# LED_strip_control.net
KiCad netlist of a schematic drawn in EAGLE
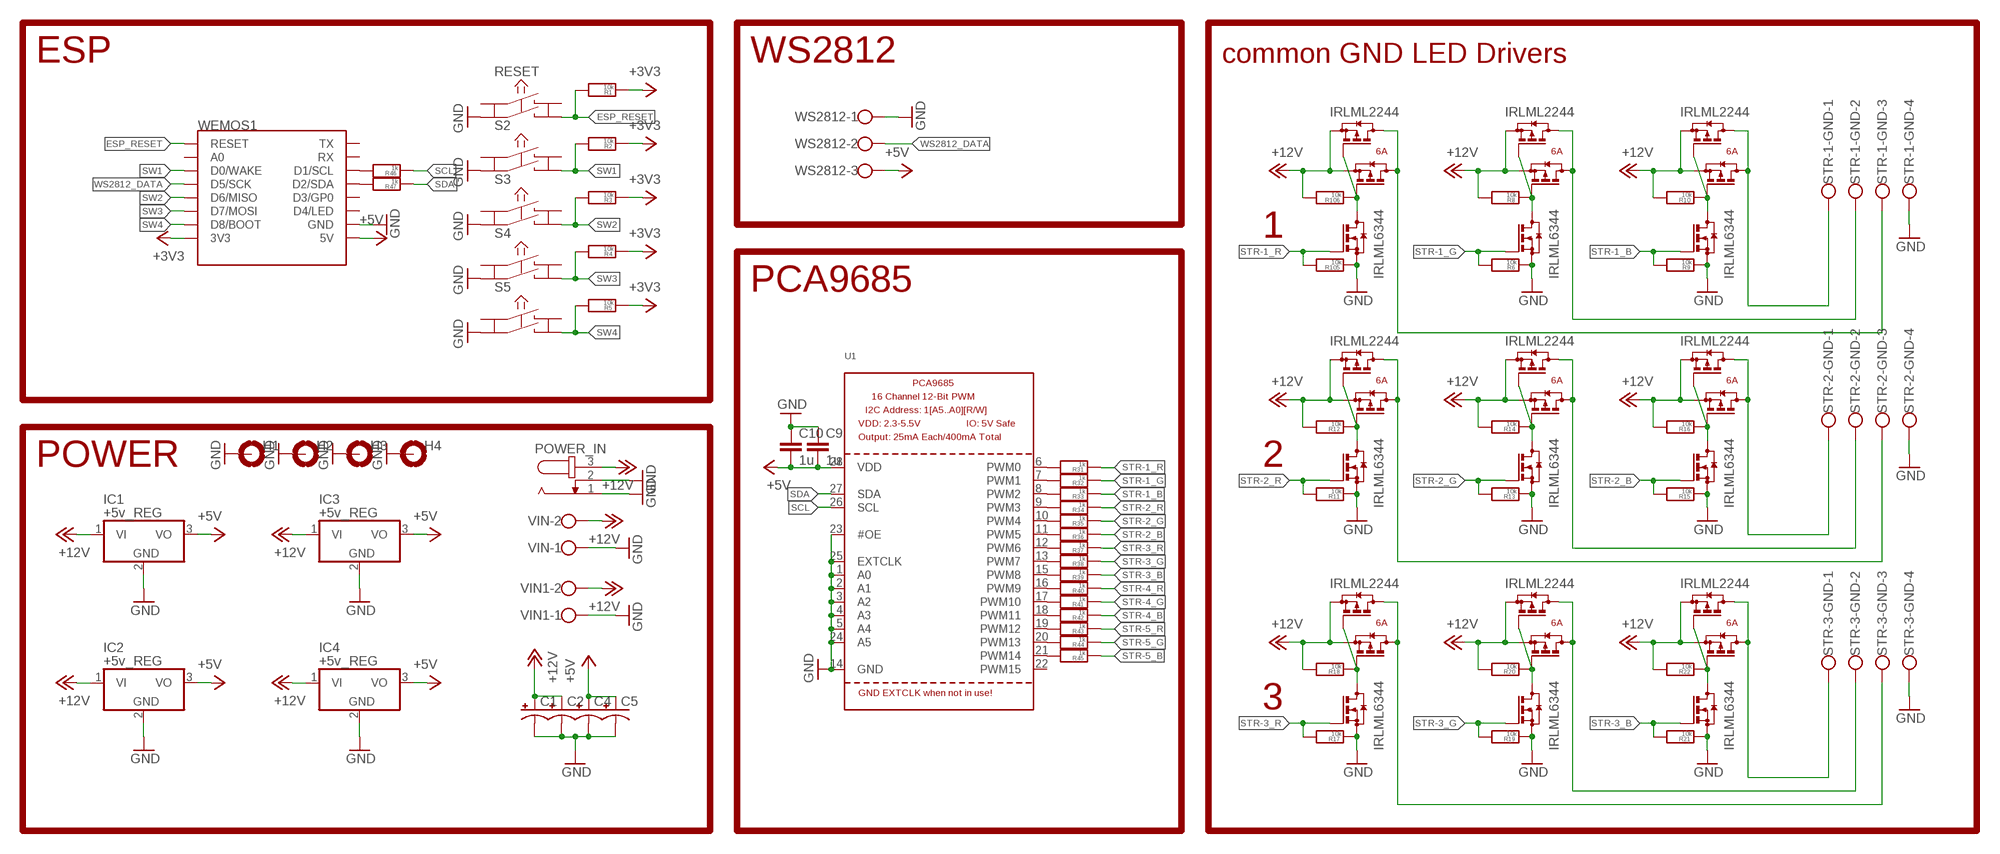
[diagram p0: schematic, sheet 1, part 1 of 2]
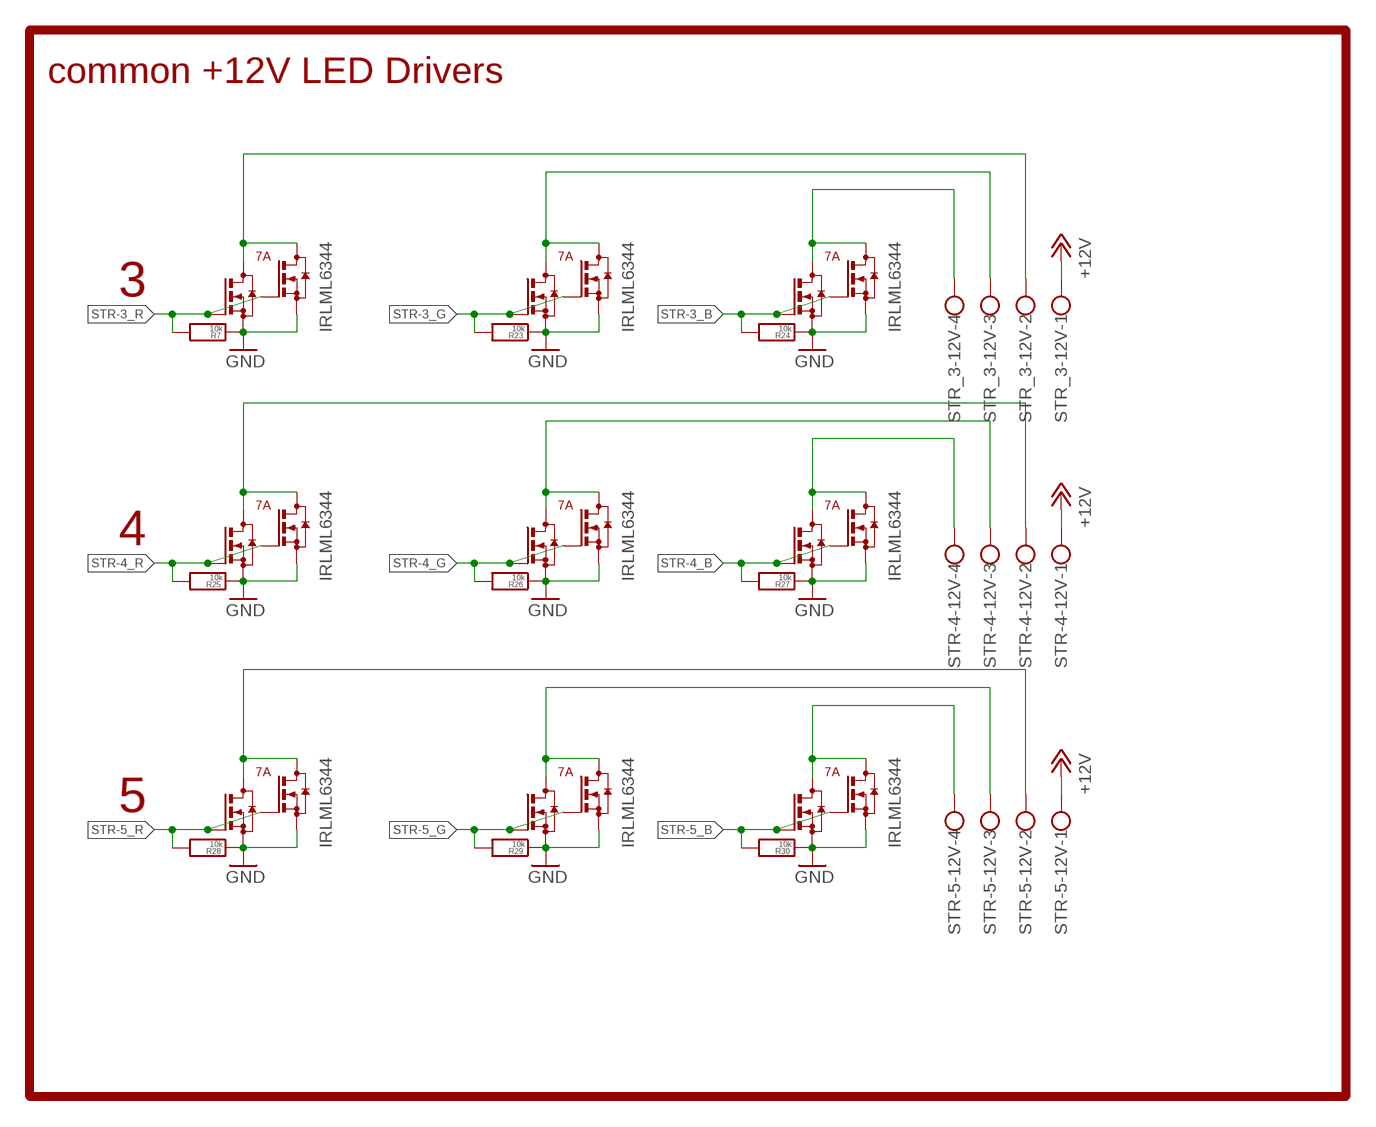
[diagram p1: schematic, sheet 1, part 2 of 2]

(export (version "E")
  (design (tool "Eeschema 10.0.6"))
  (components
    (comp (ref "C1")
      (value "CPOL-USE5-10.5")
      (footprint "eagle-import:E5-10,5@1")
      (libsource (lib "eagle-import") (part "CPOL-USE5-10.5"))
    )
    (comp (ref "C2")
      (value "CPOL-USE5-10.5")
      (footprint "eagle-import:E5-10,5@1")
      (libsource (lib "eagle-import") (part "CPOL-USE5-10.5"))
    )
    (comp (ref "C4")
      (value "CPOL-USE5-10.5")
      (footprint "eagle-import:E5-10,5@1")
      (libsource (lib "eagle-import") (part "CPOL-USE5-10.5"))
    )
    (comp (ref "C5")
      (value "CPOL-USE5-10.5")
      (footprint "eagle-import:E5-10,5@1")
      (libsource (lib "eagle-import") (part "CPOL-USE5-10.5"))
    )
    (comp (ref "C9")
      (value "1u")
      (footprint "eagle-import:C0805")
      (libsource (lib "eagle-import") (part "C-EUC0805"))
    )
    (comp (ref "C10")
      (value "1u")
      (footprint "eagle-import:C0805")
      (libsource (lib "eagle-import") (part "C-EUC0805"))
    )
    (comp (ref "H1")
      (value "MOUNT-PAD-ROUND3.2")
      (footprint "eagle-import:3,2-PAD")
      (libsource (lib "eagle-import") (part "MOUNT-PAD-ROUND3.2"))
    )
    (comp (ref "H2")
      (value "MOUNT-PAD-ROUND3.2")
      (footprint "eagle-import:3,2-PAD")
      (libsource (lib "eagle-import") (part "MOUNT-PAD-ROUND3.2"))
    )
    (comp (ref "H3")
      (value "MOUNT-PAD-ROUND3.2")
      (footprint "eagle-import:3,2-PAD")
      (libsource (lib "eagle-import") (part "MOUNT-PAD-ROUND3.2"))
    )
    (comp (ref "H4")
      (value "MOUNT-PAD-ROUND3.2")
      (footprint "eagle-import:3,2-PAD")
      (libsource (lib "eagle-import") (part "MOUNT-PAD-ROUND3.2"))
    )
    (comp (ref "IC1")
      (value "+5v_REG")
      (footprint "eagle-import:TO220V")
      (libsource (lib "eagle-import") (part "78TV6"))
    )
    (comp (ref "IC2")
      (value "+5v_REG")
      (footprint "eagle-import:TO220V")
      (libsource (lib "eagle-import") (part "78TV6"))
    )
    (comp (ref "IC3")
      (value "+5v_REG")
      (footprint "eagle-import:TO220V")
      (libsource (lib "eagle-import") (part "78TV6"))
    )
    (comp (ref "IC4")
      (value "+5v_REG")
      (footprint "eagle-import:TO220V")
      (libsource (lib "eagle-import") (part "78TV6"))
    )
    (comp (ref "POWER_IN")
      (value "RAPC7120")
      (footprint "eagle-import:RAPC712")
      (libsource (lib "eagle-import") (part "RAPC7120"))
    )
    (comp (ref "Q1")
      (value "IRLML2244")
      (footprint "eagle-import:SOT23")
      (libsource (lib "eagle-import") (part "BSS84"))
    )
    (comp (ref "Q2")
      (value "IRLML2244")
      (footprint "eagle-import:SOT23")
      (libsource (lib "eagle-import") (part "BSS84"))
    )
    (comp (ref "Q3")
      (value "IRLML6344")
      (footprint "eagle-import:SOT23")
      (libsource (lib "eagle-import") (part "BSS123"))
    )
    (comp (ref "Q4")
      (value "IRLML6344")
      (footprint "eagle-import:SOT23")
      (libsource (lib "eagle-import") (part "BSS123"))
    )
    (comp (ref "Q5")
      (value "IRLML6344")
      (footprint "eagle-import:SOT23")
      (libsource (lib "eagle-import") (part "BSS123"))
    )
    (comp (ref "Q6")
      (value "IRLML6344")
      (footprint "eagle-import:SOT23")
      (libsource (lib "eagle-import") (part "BSS123"))
    )
    (comp (ref "Q7")
      (value "IRLML2244")
      (footprint "eagle-import:SOT23")
      (libsource (lib "eagle-import") (part "BSS84"))
    )
    (comp (ref "Q8")
      (value "IRLML2244")
      (footprint "eagle-import:SOT23")
      (libsource (lib "eagle-import") (part "BSS84"))
    )
    (comp (ref "Q9")
      (value "IRLML6344")
      (footprint "eagle-import:SOT23")
      (libsource (lib "eagle-import") (part "BSS123"))
    )
    (comp (ref "Q10")
      (value "IRLML2244")
      (footprint "eagle-import:SOT23")
      (libsource (lib "eagle-import") (part "BSS84"))
    )
    (comp (ref "Q11")
      (value "IRLML2244")
      (footprint "eagle-import:SOT23")
      (libsource (lib "eagle-import") (part "BSS84"))
    )
    (comp (ref "Q12")
      (value "IRLML6344")
      (footprint "eagle-import:SOT23")
      (libsource (lib "eagle-import") (part "BSS123"))
    )
    (comp (ref "Q13")
      (value "IRLML2244")
      (footprint "eagle-import:SOT23")
      (libsource (lib "eagle-import") (part "BSS84"))
    )
    (comp (ref "Q14")
      (value "IRLML2244")
      (footprint "eagle-import:SOT23")
      (libsource (lib "eagle-import") (part "BSS84"))
    )
    (comp (ref "Q15")
      (value "IRLML6344")
      (footprint "eagle-import:SOT23")
      (libsource (lib "eagle-import") (part "BSS123"))
    )
    (comp (ref "Q16")
      (value "IRLML2244")
      (footprint "eagle-import:SOT23")
      (libsource (lib "eagle-import") (part "BSS84"))
    )
    (comp (ref "Q17")
      (value "IRLML2244")
      (footprint "eagle-import:SOT23")
      (libsource (lib "eagle-import") (part "BSS84"))
    )
    (comp (ref "Q18")
      (value "IRLML6344")
      (footprint "eagle-import:SOT23")
      (libsource (lib "eagle-import") (part "BSS123"))
    )
    (comp (ref "Q19")
      (value "IRLML2244")
      (footprint "eagle-import:SOT23")
      (libsource (lib "eagle-import") (part "BSS84"))
    )
    (comp (ref "Q20")
      (value "IRLML2244")
      (footprint "eagle-import:SOT23")
      (libsource (lib "eagle-import") (part "BSS84"))
    )
    (comp (ref "Q21")
      (value "IRLML6344")
      (footprint "eagle-import:SOT23")
      (libsource (lib "eagle-import") (part "BSS123"))
    )
    (comp (ref "Q22")
      (value "IRLML2244")
      (footprint "eagle-import:SOT23")
      (libsource (lib "eagle-import") (part "BSS84"))
    )
    (comp (ref "Q23")
      (value "IRLML2244")
      (footprint "eagle-import:SOT23")
      (libsource (lib "eagle-import") (part "BSS84"))
    )
    (comp (ref "Q24")
      (value "IRLML6344")
      (footprint "eagle-import:SOT23")
      (libsource (lib "eagle-import") (part "BSS123"))
    )
    (comp (ref "Q25")
      (value "IRLML2244")
      (footprint "eagle-import:SOT23")
      (libsource (lib "eagle-import") (part "BSS84"))
    )
    (comp (ref "Q26")
      (value "IRLML2244")
      (footprint "eagle-import:SOT23")
      (libsource (lib "eagle-import") (part "BSS84"))
    )
    (comp (ref "Q27")
      (value "IRLML6344")
      (footprint "eagle-import:SOT23")
      (libsource (lib "eagle-import") (part "BSS123"))
    )
    (comp (ref "Q28")
      (value "IRLML2244")
      (footprint "eagle-import:SOT23")
      (libsource (lib "eagle-import") (part "BSS84"))
    )
    (comp (ref "Q29")
      (value "IRLML2244")
      (footprint "eagle-import:SOT23")
      (libsource (lib "eagle-import") (part "BSS84"))
    )
    (comp (ref "Q30")
      (value "IRLML6344")
      (footprint "eagle-import:SOT23")
      (libsource (lib "eagle-import") (part "BSS123"))
    )
    (comp (ref "Q31")
      (value "IRLML6344")
      (footprint "eagle-import:SOT23")
      (libsource (lib "eagle-import") (part "BSS123"))
    )
    (comp (ref "Q32")
      (value "IRLML6344")
      (footprint "eagle-import:SOT23")
      (libsource (lib "eagle-import") (part "BSS123"))
    )
    (comp (ref "Q33")
      (value "IRLML6344")
      (footprint "eagle-import:SOT23")
      (libsource (lib "eagle-import") (part "BSS123"))
    )
    (comp (ref "Q34")
      (value "IRLML6344")
      (footprint "eagle-import:SOT23")
      (libsource (lib "eagle-import") (part "BSS123"))
    )
    (comp (ref "Q35")
      (value "IRLML6344")
      (footprint "eagle-import:SOT23")
      (libsource (lib "eagle-import") (part "BSS123"))
    )
    (comp (ref "Q36")
      (value "IRLML6344")
      (footprint "eagle-import:SOT23")
      (libsource (lib "eagle-import") (part "BSS123"))
    )
    (comp (ref "Q37")
      (value "IRLML6344")
      (footprint "eagle-import:SOT23")
      (libsource (lib "eagle-import") (part "BSS123"))
    )
    (comp (ref "Q38")
      (value "IRLML6344")
      (footprint "eagle-import:SOT23")
      (libsource (lib "eagle-import") (part "BSS123"))
    )
    (comp (ref "Q39")
      (value "IRLML6344")
      (footprint "eagle-import:SOT23")
      (libsource (lib "eagle-import") (part "BSS123"))
    )
    (comp (ref "Q40")
      (value "IRLML6344")
      (footprint "eagle-import:SOT23")
      (libsource (lib "eagle-import") (part "BSS123"))
    )
    (comp (ref "Q41")
      (value "IRLML6344")
      (footprint "eagle-import:SOT23")
      (libsource (lib "eagle-import") (part "BSS123"))
    )
    (comp (ref "Q42")
      (value "IRLML6344")
      (footprint "eagle-import:SOT23")
      (libsource (lib "eagle-import") (part "BSS123"))
    )
    (comp (ref "Q43")
      (value "IRLML6344")
      (footprint "eagle-import:SOT23")
      (libsource (lib "eagle-import") (part "BSS123"))
    )
    (comp (ref "Q44")
      (value "IRLML6344")
      (footprint "eagle-import:SOT23")
      (libsource (lib "eagle-import") (part "BSS123"))
    )
    (comp (ref "Q45")
      (value "IRLML6344")
      (footprint "eagle-import:SOT23")
      (libsource (lib "eagle-import") (part "BSS123"))
    )
    (comp (ref "R1")
      (value "10k")
      (footprint "eagle-import:R0805")
      (libsource (lib "eagle-import") (part "R-EU_R0805"))
    )
    (comp (ref "R2")
      (value "10k")
      (footprint "eagle-import:R0805")
      (libsource (lib "eagle-import") (part "R-EU_R0805"))
    )
    (comp (ref "R3")
      (value "10k")
      (footprint "eagle-import:R0805")
      (libsource (lib "eagle-import") (part "R-EU_R0805"))
    )
    (comp (ref "R4")
      (value "10k")
      (footprint "eagle-import:R0805")
      (libsource (lib "eagle-import") (part "R-EU_R0805"))
    )
    (comp (ref "R5")
      (value "10k")
      (footprint "eagle-import:R0805")
      (libsource (lib "eagle-import") (part "R-EU_R0805"))
    )
    (comp (ref "R6")
      (value "10k")
      (footprint "eagle-import:R0805")
      (libsource (lib "eagle-import") (part "R-EU_R0805"))
    )
    (comp (ref "R7")
      (value "10k")
      (footprint "eagle-import:R0805")
      (libsource (lib "eagle-import") (part "R-EU_R0805"))
    )
    (comp (ref "R8")
      (value "10k")
      (footprint "eagle-import:R0805")
      (libsource (lib "eagle-import") (part "R-EU_R0805"))
    )
    (comp (ref "R9")
      (value "10k")
      (footprint "eagle-import:R0805")
      (libsource (lib "eagle-import") (part "R-EU_R0805"))
    )
    (comp (ref "R10")
      (value "10k")
      (footprint "eagle-import:R0805")
      (libsource (lib "eagle-import") (part "R-EU_R0805"))
    )
    (comp (ref "R11")
      (value "10k")
      (footprint "eagle-import:R0805")
      (libsource (lib "eagle-import") (part "R-EU_R0805"))
    )
    (comp (ref "R12")
      (value "10k")
      (footprint "eagle-import:R0805")
      (libsource (lib "eagle-import") (part "R-EU_R0805"))
    )
    (comp (ref "R13")
      (value "10k")
      (footprint "eagle-import:R0805")
      (libsource (lib "eagle-import") (part "R-EU_R0805"))
    )
    (comp (ref "R14")
      (value "10k")
      (footprint "eagle-import:R0805")
      (libsource (lib "eagle-import") (part "R-EU_R0805"))
    )
    (comp (ref "R15")
      (value "10k")
      (footprint "eagle-import:R0805")
      (libsource (lib "eagle-import") (part "R-EU_R0805"))
    )
    (comp (ref "R16")
      (value "10k")
      (footprint "eagle-import:R0805")
      (libsource (lib "eagle-import") (part "R-EU_R0805"))
    )
    (comp (ref "R17")
      (value "10k")
      (footprint "eagle-import:R0805")
      (libsource (lib "eagle-import") (part "R-EU_R0805"))
    )
    (comp (ref "R18")
      (value "10k")
      (footprint "eagle-import:R0805")
      (libsource (lib "eagle-import") (part "R-EU_R0805"))
    )
    (comp (ref "R19")
      (value "10k")
      (footprint "eagle-import:R0805")
      (libsource (lib "eagle-import") (part "R-EU_R0805"))
    )
    (comp (ref "R20")
      (value "10k")
      (footprint "eagle-import:R0805")
      (libsource (lib "eagle-import") (part "R-EU_R0805"))
    )
    (comp (ref "R21")
      (value "10k")
      (footprint "eagle-import:R0805")
      (libsource (lib "eagle-import") (part "R-EU_R0805"))
    )
    (comp (ref "R22")
      (value "10k")
      (footprint "eagle-import:R0805")
      (libsource (lib "eagle-import") (part "R-EU_R0805"))
    )
    (comp (ref "R23")
      (value "10k")
      (footprint "eagle-import:R0805")
      (libsource (lib "eagle-import") (part "R-EU_R0805"))
    )
    (comp (ref "R24")
      (value "10k")
      (footprint "eagle-import:R0805")
      (libsource (lib "eagle-import") (part "R-EU_R0805"))
    )
    (comp (ref "R25")
      (value "10k")
      (footprint "eagle-import:R0805")
      (libsource (lib "eagle-import") (part "R-EU_R0805"))
    )
    (comp (ref "R26")
      (value "10k")
      (footprint "eagle-import:R0805")
      (libsource (lib "eagle-import") (part "R-EU_R0805"))
    )
    (comp (ref "R27")
      (value "10k")
      (footprint "eagle-import:R0805")
      (libsource (lib "eagle-import") (part "R-EU_R0805"))
    )
    (comp (ref "R28")
      (value "10k")
      (footprint "eagle-import:R0805")
      (libsource (lib "eagle-import") (part "R-EU_R0805"))
    )
    (comp (ref "R29")
      (value "10k")
      (footprint "eagle-import:R0805")
      (libsource (lib "eagle-import") (part "R-EU_R0805"))
    )
    (comp (ref "R30")
      (value "10k")
      (footprint "eagle-import:R0805")
      (libsource (lib "eagle-import") (part "R-EU_R0805"))
    )
    (comp (ref "R31")
      (value "1k")
      (footprint "eagle-import:R0805")
      (libsource (lib "eagle-import") (part "R-EU_R0805"))
    )
    (comp (ref "R32")
      (value "1k")
      (footprint "eagle-import:R0805")
      (libsource (lib "eagle-import") (part "R-EU_R0805"))
    )
    (comp (ref "R33")
      (value "1k")
      (footprint "eagle-import:R0805")
      (libsource (lib "eagle-import") (part "R-EU_R0805"))
    )
    (comp (ref "R34")
      (value "1k")
      (footprint "eagle-import:R0805")
      (libsource (lib "eagle-import") (part "R-EU_R0805"))
    )
    (comp (ref "R35")
      (value "1k")
      (footprint "eagle-import:R0805")
      (libsource (lib "eagle-import") (part "R-EU_R0805"))
    )
    (comp (ref "R36")
      (value "1k")
      (footprint "eagle-import:R0805")
      (libsource (lib "eagle-import") (part "R-EU_R0805"))
    )
    (comp (ref "R37")
      (value "1k")
      (footprint "eagle-import:R0805")
      (libsource (lib "eagle-import") (part "R-EU_R0805"))
    )
    (comp (ref "R38")
      (value "1k")
      (footprint "eagle-import:R0805")
      (libsource (lib "eagle-import") (part "R-EU_R0805"))
    )
    (comp (ref "R39")
      (value "1k")
      (footprint "eagle-import:R0805")
      (libsource (lib "eagle-import") (part "R-EU_R0805"))
    )
    (comp (ref "R40")
      (value "1k")
      (footprint "eagle-import:R0805")
      (libsource (lib "eagle-import") (part "R-EU_R0805"))
    )
    (comp (ref "R41")
      (value "1k")
      (footprint "eagle-import:R0805")
      (libsource (lib "eagle-import") (part "R-EU_R0805"))
    )
    (comp (ref "R42")
      (value "1k")
      (footprint "eagle-import:R0805")
      (libsource (lib "eagle-import") (part "R-EU_R0805"))
    )
    (comp (ref "R43")
      (value "1k")
      (footprint "eagle-import:R0805")
      (libsource (lib "eagle-import") (part "R-EU_R0805"))
    )
    (comp (ref "R44")
      (value "1k")
      (footprint "eagle-import:R0805")
      (libsource (lib "eagle-import") (part "R-EU_R0805"))
    )
    (comp (ref "R45")
      (value "1k")
      (footprint "eagle-import:R0805")
      (libsource (lib "eagle-import") (part "R-EU_R0805"))
    )
    (comp (ref "R46")
      (value "1k")
      (footprint "eagle-import:R0805")
      (libsource (lib "eagle-import") (part "R-EU_R0805"))
    )
    (comp (ref "R47")
      (value "1k")
      (footprint "eagle-import:R0805")
      (libsource (lib "eagle-import") (part "R-EU_R0805"))
    )
    (comp (ref "R105")
      (value "10k")
      (footprint "eagle-import:R0805")
      (libsource (lib "eagle-import") (part "R-EU_R0805"))
    )
    (comp (ref "R106")
      (value "10k")
      (footprint "eagle-import:R0805")
      (libsource (lib "eagle-import") (part "R-EU_R0805"))
    )
    (comp (ref "RESET")
      (value "KSM611A")
      (footprint "eagle-import:KSM611A")
      (libsource (lib "eagle-import") (part "KSM611A"))
    )
    (comp (ref "S2")
      (value "KSM611A")
      (footprint "eagle-import:KSM611A")
      (libsource (lib "eagle-import") (part "KSM611A"))
    )
    (comp (ref "S3")
      (value "KSM611A")
      (footprint "eagle-import:KSM611A")
      (libsource (lib "eagle-import") (part "KSM611A"))
    )
    (comp (ref "S4")
      (value "KSM611A")
      (footprint "eagle-import:KSM611A")
      (libsource (lib "eagle-import") (part "KSM611A"))
    )
    (comp (ref "S5")
      (value "KSM611A")
      (footprint "eagle-import:KSM611A")
      (libsource (lib "eagle-import") (part "KSM611A"))
    )
    (comp (ref "STR-1-GND")
      (value "KLEMME_4-PIN")
      (footprint "eagle-import:KLEMME_4-PIN")
      (libsource (lib "eagle-import") (part "KLEMME_4-PIN"))
    )
    (comp (ref "STR-2-GND")
      (value "KLEMME_4-PIN")
      (footprint "eagle-import:KLEMME_4-PIN")
      (libsource (lib "eagle-import") (part "KLEMME_4-PIN"))
    )
    (comp (ref "STR-3-GND")
      (value "KLEMME_4-PIN")
      (footprint "eagle-import:KLEMME_4-PIN")
      (libsource (lib "eagle-import") (part "KLEMME_4-PIN"))
    )
    (comp (ref "STR-4-12V")
      (value "KLEMME_4-PIN")
      (footprint "eagle-import:KLEMME_4-PIN")
      (libsource (lib "eagle-import") (part "KLEMME_4-PIN"))
    )
    (comp (ref "STR-5-12V")
      (value "KLEMME_4-PIN")
      (footprint "eagle-import:KLEMME_4-PIN")
      (libsource (lib "eagle-import") (part "KLEMME_4-PIN"))
    )
    (comp (ref "STR_3-12V")
      (value "KLEMME_4-PIN")
      (footprint "eagle-import:KLEMME_4-PIN")
      (libsource (lib "eagle-import") (part "KLEMME_4-PIN"))
    )
    (comp (ref "U1")
      (value "PCA9685")
      (footprint "eagle-import:TSSOP28")
      (libsource (lib "eagle-import") (part "PCA9685"))
    )
    (comp (ref "VIN")
      (value "W237-102")
      (footprint "eagle-import:W237-102")
      (fields (field (name "MPN") "237-102"))
      (libsource (lib "eagle-import") (part "W237-102"))
    )
    (comp (ref "VIN1")
      (value "W237-102")
      (footprint "eagle-import:W237-102")
      (fields (field (name "MPN") "237-102"))
      (libsource (lib "eagle-import") (part "W237-102"))
    )
    (comp (ref "WEMOS1")
      (value "WEMOS-D1-MINI")
      (footprint "eagle-import:WEMOS-D1-MINI")
      (libsource (lib "eagle-import") (part "WEMOS-D1-MINI"))
    )
    (comp (ref "WS2812")
      (value "KLEMME_3-PIN")
      (footprint "eagle-import:KLEMME_3-PIN")
      (libsource (lib "eagle-import") (part "KLEMME_3-PIN"))
    )
  )
  (nets
    (net (code "1") (name "+3V3") (class "Default")
      (node (ref "R1") (pin "1") (pinfunction "1_1") (pintype "passive"))
      (node (ref "R2") (pin "1") (pinfunction "1_1") (pintype "passive"))
      (node (ref "R3") (pin "1") (pinfunction "1_1") (pintype "passive"))
      (node (ref "R4") (pin "1") (pinfunction "1_1") (pintype "passive"))
      (node (ref "R5") (pin "1") (pinfunction "1_1") (pintype "passive"))
      (node (ref "WEMOS1") (pin "3V3") (pinfunction "3V3_3V3") (pintype "bidirectional"))
    )
    (net (code "2") (name "+5V") (class "Default")
      (node (ref "C10") (pin "2") (pinfunction "2_2") (pintype "passive"))
      (node (ref "C4") (pin "+") (pinfunction "+_+") (pintype "passive"))
      (node (ref "C5") (pin "+") (pinfunction "+_+") (pintype "passive"))
      (node (ref "C9") (pin "2") (pinfunction "2_2") (pintype "passive"))
      (node (ref "IC1") (pin "3") (pinfunction "VO_3") (pintype "passive"))
      (node (ref "IC2") (pin "3") (pinfunction "VO_3") (pintype "passive"))
      (node (ref "IC3") (pin "3") (pinfunction "VO_3") (pintype "passive"))
      (node (ref "IC4") (pin "3") (pinfunction "VO_3") (pintype "passive"))
      (node (ref "U1") (pin "28") (pinfunction "VDD_28") (pintype "power_in"))
      (node (ref "WEMOS1") (pin "5V") (pinfunction "5V_5V") (pintype "bidirectional"))
      (node (ref "WS2812") (pin "3") (pinfunction "KL_3") (pintype "passive"))
    )
    (net (code "3") (name "+12V") (class "Default")
      (node (ref "C1") (pin "+") (pinfunction "+_+") (pintype "passive"))
      (node (ref "C2") (pin "+") (pinfunction "+_+") (pintype "passive"))
      (node (ref "IC1") (pin "1") (pinfunction "VI_1") (pintype "input"))
      (node (ref "IC2") (pin "1") (pinfunction "VI_1") (pintype "input"))
      (node (ref "IC3") (pin "1") (pinfunction "VI_1") (pintype "input"))
      (node (ref "IC4") (pin "1") (pinfunction "VI_1") (pintype "input"))
      (node (ref "POWER_IN") (pin "3") (pinfunction "3_3") (pintype "passive"))
      (node (ref "Q1") (pin "2") (pinfunction "S_2") (pintype "passive"))
      (node (ref "Q10") (pin "2") (pinfunction "S_2") (pintype "passive"))
      (node (ref "Q11") (pin "2") (pinfunction "S_2") (pintype "passive"))
      (node (ref "Q13") (pin "2") (pinfunction "S_2") (pintype "passive"))
      (node (ref "Q14") (pin "2") (pinfunction "S_2") (pintype "passive"))
      (node (ref "Q16") (pin "2") (pinfunction "S_2") (pintype "passive"))
      (node (ref "Q17") (pin "2") (pinfunction "S_2") (pintype "passive"))
      (node (ref "Q19") (pin "2") (pinfunction "S_2") (pintype "passive"))
      (node (ref "Q2") (pin "2") (pinfunction "S_2") (pintype "passive"))
      (node (ref "Q20") (pin "2") (pinfunction "S_2") (pintype "passive"))
      (node (ref "Q22") (pin "2") (pinfunction "S_2") (pintype "passive"))
      (node (ref "Q23") (pin "2") (pinfunction "S_2") (pintype "passive"))
      (node (ref "Q25") (pin "2") (pinfunction "S_2") (pintype "passive"))
      (node (ref "Q26") (pin "2") (pinfunction "S_2") (pintype "passive"))
      (node (ref "Q28") (pin "2") (pinfunction "S_2") (pintype "passive"))
      (node (ref "Q29") (pin "2") (pinfunction "S_2") (pintype "passive"))
      (node (ref "Q7") (pin "2") (pinfunction "S_2") (pintype "passive"))
      (node (ref "Q8") (pin "2") (pinfunction "S_2") (pintype "passive"))
      (node (ref "R10") (pin "2") (pinfunction "2_2") (pintype "passive"))
      (node (ref "R106") (pin "2") (pinfunction "2_2") (pintype "passive"))
      (node (ref "R12") (pin "2") (pinfunction "2_2") (pintype "passive"))
      (node (ref "R14") (pin "2") (pinfunction "2_2") (pintype "passive"))
      (node (ref "R16") (pin "2") (pinfunction "2_2") (pintype "passive"))
      (node (ref "R18") (pin "2") (pinfunction "2_2") (pintype "passive"))
      (node (ref "R20") (pin "2") (pinfunction "2_2") (pintype "passive"))
      (node (ref "R22") (pin "2") (pinfunction "2_2") (pintype "passive"))
      (node (ref "R8") (pin "2") (pinfunction "2_2") (pintype "passive"))
      (node (ref "STR-4-12V") (pin "1") (pinfunction "KL_1") (pintype "passive"))
      (node (ref "STR-5-12V") (pin "1") (pinfunction "KL_1") (pintype "passive"))
      (node (ref "STR_3-12V") (pin "1") (pinfunction "KL_1") (pintype "passive"))
      (node (ref "VIN") (pin "2") (pinfunction "KL_2") (pintype "passive"))
      (node (ref "VIN1") (pin "2") (pinfunction "KL_2") (pintype "passive"))
    )
    (net (code "4") (name "ESP_RESET") (class "Default")
      (node (ref "R1") (pin "2") (pinfunction "2_2") (pintype "passive"))
      (node (ref "RESET") (pin "D") (pinfunction "D_D") (pintype "passive"))
      (node (ref "WEMOS1") (pin "RESET") (pinfunction "RESET_RESET") (pintype "bidirectional"))
    )
    (net (code "5") (name "GND") (class "Default")
      (node (ref "C1") (pin "-") (pinfunction "-_-") (pintype "passive"))
      (node (ref "C10") (pin "1") (pinfunction "1_1") (pintype "passive"))
      (node (ref "C2") (pin "-") (pinfunction "-_-") (pintype "passive"))
      (node (ref "C4") (pin "-") (pinfunction "-_-") (pintype "passive"))
      (node (ref "C5") (pin "-") (pinfunction "-_-") (pintype "passive"))
      (node (ref "C9") (pin "1") (pinfunction "1_1") (pintype "passive"))
      (node (ref "H1") (pin "B3,2") (pinfunction "MOUNT_B3,2") (pintype "passive"))
      (node (ref "H2") (pin "B3,2") (pinfunction "MOUNT_B3,2") (pintype "passive"))
      (node (ref "H3") (pin "B3,2") (pinfunction "MOUNT_B3,2") (pintype "passive"))
      (node (ref "H4") (pin "B3,2") (pinfunction "MOUNT_B3,2") (pintype "passive"))
      (node (ref "IC1") (pin "2") (pinfunction "GND_2") (pintype "passive"))
      (node (ref "IC2") (pin "2") (pinfunction "GND_2") (pintype "passive"))
      (node (ref "IC3") (pin "2") (pinfunction "GND_2") (pintype "passive"))
      (node (ref "IC4") (pin "2") (pinfunction "GND_2") (pintype "passive"))
      (node (ref "POWER_IN") (pin "1") (pinfunction "1_1") (pintype "passive"))
      (node (ref "POWER_IN") (pin "2") (pinfunction "2_2") (pintype "passive"))
      (node (ref "Q12") (pin "2") (pinfunction "S_2") (pintype "passive"))
      (node (ref "Q15") (pin "2") (pinfunction "S_2") (pintype "passive"))
      (node (ref "Q18") (pin "2") (pinfunction "S_2") (pintype "passive"))
      (node (ref "Q21") (pin "2") (pinfunction "S_2") (pintype "passive"))
      (node (ref "Q24") (pin "2") (pinfunction "S_2") (pintype "passive"))
      (node (ref "Q27") (pin "2") (pinfunction "S_2") (pintype "passive"))
      (node (ref "Q3") (pin "2") (pinfunction "S_2") (pintype "passive"))
      (node (ref "Q30") (pin "2") (pinfunction "S_2") (pintype "passive"))
      (node (ref "Q31") (pin "2") (pinfunction "S_2") (pintype "passive"))
      (node (ref "Q32") (pin "2") (pinfunction "S_2") (pintype "passive"))
      (node (ref "Q33") (pin "2") (pinfunction "S_2") (pintype "passive"))
      (node (ref "Q34") (pin "2") (pinfunction "S_2") (pintype "passive"))
      (node (ref "Q35") (pin "2") (pinfunction "S_2") (pintype "passive"))
      (node (ref "Q36") (pin "2") (pinfunction "S_2") (pintype "passive"))
      (node (ref "Q37") (pin "2") (pinfunction "S_2") (pintype "passive"))
      (node (ref "Q38") (pin "2") (pinfunction "S_2") (pintype "passive"))
      (node (ref "Q39") (pin "2") (pinfunction "S_2") (pintype "passive"))
      (node (ref "Q4") (pin "2") (pinfunction "S_2") (pintype "passive"))
      (node (ref "Q40") (pin "2") (pinfunction "S_2") (pintype "passive"))
      (node (ref "Q41") (pin "2") (pinfunction "S_2") (pintype "passive"))
      (node (ref "Q42") (pin "2") (pinfunction "S_2") (pintype "passive"))
      (node (ref "Q43") (pin "2") (pinfunction "S_2") (pintype "passive"))
      (node (ref "Q44") (pin "2") (pinfunction "S_2") (pintype "passive"))
      (node (ref "Q45") (pin "2") (pinfunction "S_2") (pintype "passive"))
      (node (ref "Q5") (pin "2") (pinfunction "S_2") (pintype "passive"))
      (node (ref "Q6") (pin "2") (pinfunction "S_2") (pintype "passive"))
      (node (ref "Q9") (pin "2") (pinfunction "S_2") (pintype "passive"))
      (node (ref "R105") (pin "1") (pinfunction "1_1") (pintype "passive"))
      (node (ref "R11") (pin "1") (pinfunction "1_1") (pintype "passive"))
      (node (ref "R13") (pin "1") (pinfunction "1_1") (pintype "passive"))
      (node (ref "R15") (pin "1") (pinfunction "1_1") (pintype "passive"))
      (node (ref "R17") (pin "1") (pinfunction "1_1") (pintype "passive"))
      (node (ref "R19") (pin "1") (pinfunction "1_1") (pintype "passive"))
      (node (ref "R21") (pin "1") (pinfunction "1_1") (pintype "passive"))
      (node (ref "R23") (pin "1") (pinfunction "1_1") (pintype "passive"))
      (node (ref "R24") (pin "1") (pinfunction "1_1") (pintype "passive"))
      (node (ref "R25") (pin "1") (pinfunction "1_1") (pintype "passive"))
      (node (ref "R26") (pin "1") (pinfunction "1_1") (pintype "passive"))
      (node (ref "R27") (pin "1") (pinfunction "1_1") (pintype "passive"))
      (node (ref "R28") (pin "1") (pinfunction "1_1") (pintype "passive"))
      (node (ref "R29") (pin "1") (pinfunction "1_1") (pintype "passive"))
      (node (ref "R30") (pin "1") (pinfunction "1_1") (pintype "passive"))
      (node (ref "R6") (pin "1") (pinfunction "1_1") (pintype "passive"))
      (node (ref "R7") (pin "1") (pinfunction "1_1") (pintype "passive"))
      (node (ref "R9") (pin "1") (pinfunction "1_1") (pintype "passive"))
      (node (ref "RESET") (pin "C") (pinfunction "C_C") (pintype "passive"))
      (node (ref "S2") (pin "C") (pinfunction "C_C") (pintype "passive"))
      (node (ref "S3") (pin "C") (pinfunction "C_C") (pintype "passive"))
      (node (ref "S4") (pin "C") (pinfunction "C_C") (pintype "passive"))
      (node (ref "S5") (pin "C") (pinfunction "C_C") (pintype "passive"))
      (node (ref "STR-1-GND") (pin "4") (pinfunction "KL_4") (pintype "passive"))
      (node (ref "STR-2-GND") (pin "4") (pinfunction "KL_4") (pintype "passive"))
      (node (ref "STR-3-GND") (pin "4") (pinfunction "KL_4") (pintype "passive"))
      (node (ref "U1") (pin "1") (pinfunction "A0_1") (pintype "bidirectional"))
      (node (ref "U1") (pin "14") (pinfunction "GND_14") (pintype "power_in"))
      (node (ref "U1") (pin "2") (pinfunction "A1_2") (pintype "bidirectional"))
      (node (ref "U1") (pin "23") (pinfunction "#OE_23") (pintype "input"))
      (node (ref "U1") (pin "24") (pinfunction "A5_24") (pintype "bidirectional"))
      (node (ref "U1") (pin "25") (pinfunction "EXTCLK_25") (pintype "input"))
      (node (ref "U1") (pin "3") (pinfunction "A2_3") (pintype "bidirectional"))
      (node (ref "U1") (pin "4") (pinfunction "A3_4") (pintype "bidirectional"))
      (node (ref "U1") (pin "5") (pinfunction "A4_5") (pintype "bidirectional"))
      (node (ref "VIN") (pin "1") (pinfunction "KL_1") (pintype "passive"))
      (node (ref "VIN1") (pin "1") (pinfunction "KL_1") (pintype "passive"))
      (node (ref "WEMOS1") (pin "GND") (pinfunction "GND_GND") (pintype "bidirectional"))
      (node (ref "WS2812") (pin "1") (pinfunction "KL_1") (pintype "passive"))
    )
    (net (code "6") (name "Net-(Q1-D)") (class "Default")
      (node (ref "Q1") (pin "3") (pinfunction "D_3") (pintype "passive"))
      (node (ref "Q2") (pin "3") (pinfunction "D_3") (pintype "passive"))
      (node (ref "STR-1-GND") (pin "3") (pinfunction "KL_3") (pintype "passive"))
    )
    (net (code "7") (name "Net-(Q1-G)") (class "Default")
      (node (ref "Q1") (pin "1") (pinfunction "G_1") (pintype "passive"))
      (node (ref "Q2") (pin "1") (pinfunction "G_1") (pintype "passive"))
      (node (ref "Q4") (pin "3") (pinfunction "D_3") (pintype "passive"))
      (node (ref "R106") (pin "1") (pinfunction "1_1") (pintype "passive"))
    )
    (net (code "8") (name "Net-(Q3-D)") (class "Default")
      (node (ref "Q3") (pin "3") (pinfunction "D_3") (pintype "passive"))
      (node (ref "Q5") (pin "3") (pinfunction "D_3") (pintype "passive"))
      (node (ref "STR_3-12V") (pin "2") (pinfunction "KL_2") (pintype "passive"))
    )
    (net (code "9") (name "Net-(Q6-D)") (class "Default")
      (node (ref "Q6") (pin "3") (pinfunction "D_3") (pintype "passive"))
      (node (ref "Q7") (pin "1") (pinfunction "G_1") (pintype "passive"))
      (node (ref "Q8") (pin "1") (pinfunction "G_1") (pintype "passive"))
      (node (ref "R8") (pin "1") (pinfunction "1_1") (pintype "passive"))
    )
    (net (code "10") (name "Net-(Q7-D)") (class "Default")
      (node (ref "Q7") (pin "3") (pinfunction "D_3") (pintype "passive"))
      (node (ref "Q8") (pin "3") (pinfunction "D_3") (pintype "passive"))
      (node (ref "STR-1-GND") (pin "2") (pinfunction "KL_2") (pintype "passive"))
    )
    (net (code "11") (name "Net-(Q10-D)") (class "Default")
      (node (ref "Q10") (pin "3") (pinfunction "D_3") (pintype "passive"))
      (node (ref "Q11") (pin "3") (pinfunction "D_3") (pintype "passive"))
      (node (ref "STR-1-GND") (pin "1") (pinfunction "KL_1") (pintype "passive"))
    )
    (net (code "12") (name "Net-(Q10-G)") (class "Default")
      (node (ref "Q10") (pin "1") (pinfunction "G_1") (pintype "passive"))
      (node (ref "Q11") (pin "1") (pinfunction "G_1") (pintype "passive"))
      (node (ref "Q9") (pin "3") (pinfunction "D_3") (pintype "passive"))
      (node (ref "R10") (pin "1") (pinfunction "1_1") (pintype "passive"))
    )
    (net (code "13") (name "Net-(Q12-D)") (class "Default")
      (node (ref "Q12") (pin "3") (pinfunction "D_3") (pintype "passive"))
      (node (ref "Q13") (pin "1") (pinfunction "G_1") (pintype "passive"))
      (node (ref "Q14") (pin "1") (pinfunction "G_1") (pintype "passive"))
      (node (ref "R12") (pin "1") (pinfunction "1_1") (pintype "passive"))
    )
    (net (code "14") (name "Net-(Q13-D)") (class "Default")
      (node (ref "Q13") (pin "3") (pinfunction "D_3") (pintype "passive"))
      (node (ref "Q14") (pin "3") (pinfunction "D_3") (pintype "passive"))
      (node (ref "STR-2-GND") (pin "3") (pinfunction "KL_3") (pintype "passive"))
    )
    (net (code "15") (name "Net-(Q15-D)") (class "Default")
      (node (ref "Q15") (pin "3") (pinfunction "D_3") (pintype "passive"))
      (node (ref "Q16") (pin "1") (pinfunction "G_1") (pintype "passive"))
      (node (ref "Q17") (pin "1") (pinfunction "G_1") (pintype "passive"))
      (node (ref "R14") (pin "1") (pinfunction "1_1") (pintype "passive"))
    )
    (net (code "16") (name "Net-(Q16-D)") (class "Default")
      (node (ref "Q16") (pin "3") (pinfunction "D_3") (pintype "passive"))
      (node (ref "Q17") (pin "3") (pinfunction "D_3") (pintype "passive"))
      (node (ref "STR-2-GND") (pin "2") (pinfunction "KL_2") (pintype "passive"))
    )
    (net (code "17") (name "Net-(Q18-D)") (class "Default")
      (node (ref "Q18") (pin "3") (pinfunction "D_3") (pintype "passive"))
      (node (ref "Q19") (pin "1") (pinfunction "G_1") (pintype "passive"))
      (node (ref "Q20") (pin "1") (pinfunction "G_1") (pintype "passive"))
      (node (ref "R16") (pin "1") (pinfunction "1_1") (pintype "passive"))
    )
    (net (code "18") (name "Net-(Q19-D)") (class "Default")
      (node (ref "Q19") (pin "3") (pinfunction "D_3") (pintype "passive"))
      (node (ref "Q20") (pin "3") (pinfunction "D_3") (pintype "passive"))
      (node (ref "STR-2-GND") (pin "1") (pinfunction "KL_1") (pintype "passive"))
    )
    (net (code "19") (name "Net-(Q21-D)") (class "Default")
      (node (ref "Q21") (pin "3") (pinfunction "D_3") (pintype "passive"))
      (node (ref "Q22") (pin "1") (pinfunction "G_1") (pintype "passive"))
      (node (ref "Q23") (pin "1") (pinfunction "G_1") (pintype "passive"))
      (node (ref "R18") (pin "1") (pinfunction "1_1") (pintype "passive"))
    )
    (net (code "20") (name "Net-(Q22-D)") (class "Default")
      (node (ref "Q22") (pin "3") (pinfunction "D_3") (pintype "passive"))
      (node (ref "Q23") (pin "3") (pinfunction "D_3") (pintype "passive"))
      (node (ref "STR-3-GND") (pin "3") (pinfunction "KL_3") (pintype "passive"))
    )
    (net (code "21") (name "Net-(Q24-D)") (class "Default")
      (node (ref "Q24") (pin "3") (pinfunction "D_3") (pintype "passive"))
      (node (ref "Q25") (pin "1") (pinfunction "G_1") (pintype "passive"))
      (node (ref "Q26") (pin "1") (pinfunction "G_1") (pintype "passive"))
      (node (ref "R20") (pin "1") (pinfunction "1_1") (pintype "passive"))
    )
    (net (code "22") (name "Net-(Q25-D)") (class "Default")
      (node (ref "Q25") (pin "3") (pinfunction "D_3") (pintype "passive"))
      (node (ref "Q26") (pin "3") (pinfunction "D_3") (pintype "passive"))
      (node (ref "STR-3-GND") (pin "2") (pinfunction "KL_2") (pintype "passive"))
    )
    (net (code "23") (name "Net-(Q27-D)") (class "Default")
      (node (ref "Q27") (pin "3") (pinfunction "D_3") (pintype "passive"))
      (node (ref "Q28") (pin "1") (pinfunction "G_1") (pintype "passive"))
      (node (ref "Q29") (pin "1") (pinfunction "G_1") (pintype "passive"))
      (node (ref "R22") (pin "1") (pinfunction "1_1") (pintype "passive"))
    )
    (net (code "24") (name "Net-(Q28-D)") (class "Default")
      (node (ref "Q28") (pin "3") (pinfunction "D_3") (pintype "passive"))
      (node (ref "Q29") (pin "3") (pinfunction "D_3") (pintype "passive"))
      (node (ref "STR-3-GND") (pin "1") (pinfunction "KL_1") (pintype "passive"))
    )
    (net (code "25") (name "Net-(Q30-D)") (class "Default")
      (node (ref "Q30") (pin "3") (pinfunction "D_3") (pintype "passive"))
      (node (ref "Q31") (pin "3") (pinfunction "D_3") (pintype "passive"))
      (node (ref "STR_3-12V") (pin "3") (pinfunction "KL_3") (pintype "passive"))
    )
    (net (code "26") (name "Net-(Q32-D)") (class "Default")
      (node (ref "Q32") (pin "3") (pinfunction "D_3") (pintype "passive"))
      (node (ref "Q33") (pin "3") (pinfunction "D_3") (pintype "passive"))
      (node (ref "STR_3-12V") (pin "4") (pinfunction "KL_4") (pintype "passive"))
    )
    (net (code "27") (name "Net-(Q34-D)") (class "Default")
      (node (ref "Q34") (pin "3") (pinfunction "D_3") (pintype "passive"))
      (node (ref "Q35") (pin "3") (pinfunction "D_3") (pintype "passive"))
      (node (ref "STR-4-12V") (pin "2") (pinfunction "KL_2") (pintype "passive"))
    )
    (net (code "28") (name "Net-(Q36-D)") (class "Default")
      (node (ref "Q36") (pin "3") (pinfunction "D_3") (pintype "passive"))
      (node (ref "Q37") (pin "3") (pinfunction "D_3") (pintype "passive"))
      (node (ref "STR-4-12V") (pin "3") (pinfunction "KL_3") (pintype "passive"))
    )
    (net (code "29") (name "Net-(Q38-D)") (class "Default")
      (node (ref "Q38") (pin "3") (pinfunction "D_3") (pintype "passive"))
      (node (ref "Q39") (pin "3") (pinfunction "D_3") (pintype "passive"))
      (node (ref "STR-4-12V") (pin "4") (pinfunction "KL_4") (pintype "passive"))
    )
    (net (code "30") (name "Net-(Q40-D)") (class "Default")
      (node (ref "Q40") (pin "3") (pinfunction "D_3") (pintype "passive"))
      (node (ref "Q41") (pin "3") (pinfunction "D_3") (pintype "passive"))
      (node (ref "STR-5-12V") (pin "2") (pinfunction "KL_2") (pintype "passive"))
    )
    (net (code "31") (name "Net-(Q42-D)") (class "Default")
      (node (ref "Q42") (pin "3") (pinfunction "D_3") (pintype "passive"))
      (node (ref "Q43") (pin "3") (pinfunction "D_3") (pintype "passive"))
      (node (ref "STR-5-12V") (pin "3") (pinfunction "KL_3") (pintype "passive"))
    )
    (net (code "32") (name "Net-(Q44-D)") (class "Default")
      (node (ref "Q44") (pin "3") (pinfunction "D_3") (pintype "passive"))
      (node (ref "Q45") (pin "3") (pinfunction "D_3") (pintype "passive"))
      (node (ref "STR-5-12V") (pin "4") (pinfunction "KL_4") (pintype "passive"))
    )
    (net (code "33") (name "Net-(U1-PWM0)") (class "Default")
      (node (ref "R31") (pin "2") (pinfunction "2_2") (pintype "passive"))
      (node (ref "U1") (pin "6") (pinfunction "PWM0_6") (pintype "output"))
    )
    (net (code "34") (name "Net-(U1-PWM1)") (class "Default")
      (node (ref "R32") (pin "2") (pinfunction "2_2") (pintype "passive"))
      (node (ref "U1") (pin "7") (pinfunction "PWM1_7") (pintype "output"))
    )
    (net (code "35") (name "Net-(U1-PWM2)") (class "Default")
      (node (ref "R33") (pin "2") (pinfunction "2_2") (pintype "passive"))
      (node (ref "U1") (pin "8") (pinfunction "PWM2_8") (pintype "output"))
    )
    (net (code "36") (name "Net-(U1-PWM3)") (class "Default")
      (node (ref "R34") (pin "2") (pinfunction "2_2") (pintype "passive"))
      (node (ref "U1") (pin "9") (pinfunction "PWM3_9") (pintype "output"))
    )
    (net (code "37") (name "Net-(U1-PWM4)") (class "Default")
      (node (ref "R35") (pin "2") (pinfunction "2_2") (pintype "passive"))
      (node (ref "U1") (pin "10") (pinfunction "PWM4_10") (pintype "output"))
    )
    (net (code "38") (name "Net-(U1-PWM5)") (class "Default")
      (node (ref "R36") (pin "2") (pinfunction "2_2") (pintype "passive"))
      (node (ref "U1") (pin "11") (pinfunction "PWM5_11") (pintype "output"))
    )
    (net (code "39") (name "Net-(U1-PWM6)") (class "Default")
      (node (ref "R37") (pin "2") (pinfunction "2_2") (pintype "passive"))
      (node (ref "U1") (pin "12") (pinfunction "PWM6_12") (pintype "output"))
    )
    (net (code "40") (name "Net-(U1-PWM7)") (class "Default")
      (node (ref "R38") (pin "2") (pinfunction "2_2") (pintype "passive"))
      (node (ref "U1") (pin "13") (pinfunction "PWM7_13") (pintype "output"))
    )
    (net (code "41") (name "Net-(U1-PWM8)") (class "Default")
      (node (ref "R39") (pin "2") (pinfunction "2_2") (pintype "passive"))
      (node (ref "U1") (pin "15") (pinfunction "PWM8_15") (pintype "output"))
    )
    (net (code "42") (name "Net-(U1-PWM9)") (class "Default")
      (node (ref "R40") (pin "2") (pinfunction "2_2") (pintype "passive"))
      (node (ref "U1") (pin "16") (pinfunction "PWM9_16") (pintype "output"))
    )
    (net (code "43") (name "Net-(U1-PWM10)") (class "Default")
      (node (ref "R41") (pin "2") (pinfunction "2_2") (pintype "passive"))
      (node (ref "U1") (pin "17") (pinfunction "PWM10_17") (pintype "output"))
    )
    (net (code "44") (name "Net-(U1-PWM11)") (class "Default")
      (node (ref "R42") (pin "2") (pinfunction "2_2") (pintype "passive"))
      (node (ref "U1") (pin "18") (pinfunction "PWM11_18") (pintype "output"))
    )
    (net (code "45") (name "Net-(U1-PWM12)") (class "Default")
      (node (ref "R43") (pin "2") (pinfunction "2_2") (pintype "passive"))
      (node (ref "U1") (pin "19") (pinfunction "PWM12_19") (pintype "output"))
    )
    (net (code "46") (name "Net-(U1-PWM13)") (class "Default")
      (node (ref "R44") (pin "2") (pinfunction "2_2") (pintype "passive"))
      (node (ref "U1") (pin "20") (pinfunction "PWM13_20") (pintype "output"))
    )
    (net (code "47") (name "Net-(U1-PWM14)") (class "Default")
      (node (ref "R45") (pin "2") (pinfunction "2_2") (pintype "passive"))
      (node (ref "U1") (pin "21") (pinfunction "PWM14_21") (pintype "output"))
    )
    (net (code "48") (name "Net-(WEMOS1-D1{slash}SCL)") (class "Default")
      (node (ref "R46") (pin "2") (pinfunction "2_2") (pintype "passive"))
      (node (ref "WEMOS1") (pin "D1") (pinfunction "D1/SCL_D1") (pintype "bidirectional"))
    )
    (net (code "49") (name "Net-(WEMOS1-D2{slash}SDA)") (class "Default")
      (node (ref "R47") (pin "2") (pinfunction "2_2") (pintype "passive"))
      (node (ref "WEMOS1") (pin "D2") (pinfunction "D2/SDA_D2") (pintype "bidirectional"))
    )
    (net (code "50") (name "SCL") (class "Default")
      (node (ref "R46") (pin "1") (pinfunction "1_1") (pintype "passive"))
      (node (ref "U1") (pin "26") (pinfunction "SCL_26") (pintype "bidirectional"))
    )
    (net (code "51") (name "SDA") (class "Default")
      (node (ref "R47") (pin "1") (pinfunction "1_1") (pintype "passive"))
      (node (ref "U1") (pin "27") (pinfunction "SDA_27") (pintype "bidirectional"))
    )
    (net (code "52") (name "STR-1_B") (class "Default")
      (node (ref "Q9") (pin "1") (pinfunction "G_1") (pintype "passive"))
      (node (ref "R33") (pin "1") (pinfunction "1_1") (pintype "passive"))
      (node (ref "R9") (pin "2") (pinfunction "2_2") (pintype "passive"))
    )
    (net (code "53") (name "STR-1_G") (class "Default")
      (node (ref "Q6") (pin "1") (pinfunction "G_1") (pintype "passive"))
      (node (ref "R32") (pin "1") (pinfunction "1_1") (pintype "passive"))
      (node (ref "R6") (pin "2") (pinfunction "2_2") (pintype "passive"))
    )
    (net (code "54") (name "STR-1_R") (class "Default")
      (node (ref "Q4") (pin "1") (pinfunction "G_1") (pintype "passive"))
      (node (ref "R105") (pin "2") (pinfunction "2_2") (pintype "passive"))
      (node (ref "R31") (pin "1") (pinfunction "1_1") (pintype "passive"))
    )
    (net (code "55") (name "STR-2_B") (class "Default")
      (node (ref "Q18") (pin "1") (pinfunction "G_1") (pintype "passive"))
      (node (ref "R15") (pin "2") (pinfunction "2_2") (pintype "passive"))
      (node (ref "R36") (pin "1") (pinfunction "1_1") (pintype "passive"))
    )
    (net (code "56") (name "STR-2_G") (class "Default")
      (node (ref "Q15") (pin "1") (pinfunction "G_1") (pintype "passive"))
      (node (ref "R13") (pin "2") (pinfunction "2_2") (pintype "passive"))
      (node (ref "R35") (pin "1") (pinfunction "1_1") (pintype "passive"))
    )
    (net (code "57") (name "STR-2_R") (class "Default")
      (node (ref "Q12") (pin "1") (pinfunction "G_1") (pintype "passive"))
      (node (ref "R11") (pin "2") (pinfunction "2_2") (pintype "passive"))
      (node (ref "R34") (pin "1") (pinfunction "1_1") (pintype "passive"))
    )
    (net (code "58") (name "STR-3_B") (class "Default")
      (node (ref "Q27") (pin "1") (pinfunction "G_1") (pintype "passive"))
      (node (ref "Q32") (pin "1") (pinfunction "G_1") (pintype "passive"))
      (node (ref "Q33") (pin "1") (pinfunction "G_1") (pintype "passive"))
      (node (ref "R21") (pin "2") (pinfunction "2_2") (pintype "passive"))
      (node (ref "R24") (pin "2") (pinfunction "2_2") (pintype "passive"))
      (node (ref "R39") (pin "1") (pinfunction "1_1") (pintype "passive"))
    )
    (net (code "59") (name "STR-3_G") (class "Default")
      (node (ref "Q24") (pin "1") (pinfunction "G_1") (pintype "passive"))
      (node (ref "Q30") (pin "1") (pinfunction "G_1") (pintype "passive"))
      (node (ref "Q31") (pin "1") (pinfunction "G_1") (pintype "passive"))
      (node (ref "R19") (pin "2") (pinfunction "2_2") (pintype "passive"))
      (node (ref "R23") (pin "2") (pinfunction "2_2") (pintype "passive"))
      (node (ref "R38") (pin "1") (pinfunction "1_1") (pintype "passive"))
    )
    (net (code "60") (name "STR-3_R") (class "Default")
      (node (ref "Q21") (pin "1") (pinfunction "G_1") (pintype "passive"))
      (node (ref "Q3") (pin "1") (pinfunction "G_1") (pintype "passive"))
      (node (ref "Q5") (pin "1") (pinfunction "G_1") (pintype "passive"))
      (node (ref "R17") (pin "2") (pinfunction "2_2") (pintype "passive"))
      (node (ref "R37") (pin "1") (pinfunction "1_1") (pintype "passive"))
      (node (ref "R7") (pin "2") (pinfunction "2_2") (pintype "passive"))
    )
    (net (code "61") (name "STR-4_B") (class "Default")
      (node (ref "Q38") (pin "1") (pinfunction "G_1") (pintype "passive"))
      (node (ref "Q39") (pin "1") (pinfunction "G_1") (pintype "passive"))
      (node (ref "R27") (pin "2") (pinfunction "2_2") (pintype "passive"))
      (node (ref "R42") (pin "1") (pinfunction "1_1") (pintype "passive"))
    )
    (net (code "62") (name "STR-4_G") (class "Default")
      (node (ref "Q36") (pin "1") (pinfunction "G_1") (pintype "passive"))
      (node (ref "Q37") (pin "1") (pinfunction "G_1") (pintype "passive"))
      (node (ref "R26") (pin "2") (pinfunction "2_2") (pintype "passive"))
      (node (ref "R41") (pin "1") (pinfunction "1_1") (pintype "passive"))
    )
    (net (code "63") (name "STR-4_R") (class "Default")
      (node (ref "Q34") (pin "1") (pinfunction "G_1") (pintype "passive"))
      (node (ref "Q35") (pin "1") (pinfunction "G_1") (pintype "passive"))
      (node (ref "R25") (pin "2") (pinfunction "2_2") (pintype "passive"))
      (node (ref "R40") (pin "1") (pinfunction "1_1") (pintype "passive"))
    )
    (net (code "64") (name "STR-5_B") (class "Default")
      (node (ref "Q44") (pin "1") (pinfunction "G_1") (pintype "passive"))
      (node (ref "Q45") (pin "1") (pinfunction "G_1") (pintype "passive"))
      (node (ref "R30") (pin "2") (pinfunction "2_2") (pintype "passive"))
      (node (ref "R45") (pin "1") (pinfunction "1_1") (pintype "passive"))
    )
    (net (code "65") (name "STR-5_G") (class "Default")
      (node (ref "Q42") (pin "1") (pinfunction "G_1") (pintype "passive"))
      (node (ref "Q43") (pin "1") (pinfunction "G_1") (pintype "passive"))
      (node (ref "R29") (pin "2") (pinfunction "2_2") (pintype "passive"))
      (node (ref "R44") (pin "1") (pinfunction "1_1") (pintype "passive"))
    )
    (net (code "66") (name "STR-5_R") (class "Default")
      (node (ref "Q40") (pin "1") (pinfunction "G_1") (pintype "passive"))
      (node (ref "Q41") (pin "1") (pinfunction "G_1") (pintype "passive"))
      (node (ref "R28") (pin "2") (pinfunction "2_2") (pintype "passive"))
      (node (ref "R43") (pin "1") (pinfunction "1_1") (pintype "passive"))
    )
    (net (code "67") (name "SW1") (class "Default")
      (node (ref "R2") (pin "2") (pinfunction "2_2") (pintype "passive"))
      (node (ref "S2") (pin "D") (pinfunction "D_D") (pintype "passive"))
      (node (ref "WEMOS1") (pin "D0") (pinfunction "D0/WAKE_D0") (pintype "bidirectional"))
    )
    (net (code "68") (name "SW2") (class "Default")
      (node (ref "R3") (pin "2") (pinfunction "2_2") (pintype "passive"))
      (node (ref "S3") (pin "D") (pinfunction "D_D") (pintype "passive"))
      (node (ref "WEMOS1") (pin "D6") (pinfunction "D6/MISO_D6") (pintype "bidirectional"))
    )
    (net (code "69") (name "SW3") (class "Default")
      (node (ref "R4") (pin "2") (pinfunction "2_2") (pintype "passive"))
      (node (ref "S4") (pin "D") (pinfunction "D_D") (pintype "passive"))
      (node (ref "WEMOS1") (pin "D7") (pinfunction "D7/MOSI_D7") (pintype "bidirectional"))
    )
    (net (code "70") (name "SW4") (class "Default")
      (node (ref "R5") (pin "2") (pinfunction "2_2") (pintype "passive"))
      (node (ref "S5") (pin "D") (pinfunction "D_D") (pintype "passive"))
      (node (ref "WEMOS1") (pin "D8") (pinfunction "D8/BOOT_D8") (pintype "bidirectional"))
    )
    (net (code "71") (name "WS2812_DATA") (class "Default")
      (node (ref "WEMOS1") (pin "D5") (pinfunction "D5/SCK_D5") (pintype "bidirectional"))
      (node (ref "WS2812") (pin "2") (pinfunction "KL_2") (pintype "passive"))
    )
    (net (code "72") (name "unconnected-(RESET-PadA)") (class "Default")
      (node (ref "RESET") (pin "A") (pinfunction "A_A") (pintype "passive"))
    )
    (net (code "73") (name "unconnected-(RESET-PadB)") (class "Default")
      (node (ref "RESET") (pin "B") (pinfunction "B_B") (pintype "passive"))
    )
    (net (code "74") (name "unconnected-(S2-PadA)") (class "Default")
      (node (ref "S2") (pin "A") (pinfunction "A_A") (pintype "passive"))
    )
    (net (code "75") (name "unconnected-(S2-PadB)") (class "Default")
      (node (ref "S2") (pin "B") (pinfunction "B_B") (pintype "passive"))
    )
    (net (code "76") (name "unconnected-(S3-PadA)") (class "Default")
      (node (ref "S3") (pin "A") (pinfunction "A_A") (pintype "passive"))
    )
    (net (code "77") (name "unconnected-(S3-PadB)") (class "Default")
      (node (ref "S3") (pin "B") (pinfunction "B_B") (pintype "passive"))
    )
    (net (code "78") (name "unconnected-(S4-PadA)") (class "Default")
      (node (ref "S4") (pin "A") (pinfunction "A_A") (pintype "passive"))
    )
    (net (code "79") (name "unconnected-(S4-PadB)") (class "Default")
      (node (ref "S4") (pin "B") (pinfunction "B_B") (pintype "passive"))
    )
    (net (code "80") (name "unconnected-(S5-PadA)") (class "Default")
      (node (ref "S5") (pin "A") (pinfunction "A_A") (pintype "passive"))
    )
    (net (code "81") (name "unconnected-(S5-PadB)") (class "Default")
      (node (ref "S5") (pin "B") (pinfunction "B_B") (pintype "passive"))
    )
    (net (code "82") (name "unconnected-(U1-PWM15-Pad22)") (class "Default")
      (node (ref "U1") (pin "22") (pinfunction "PWM15_22") (pintype "output"))
    )
    (net (code "83") (name "unconnected-(WEMOS1-D3{slash}GP0-PadD3)") (class "Default")
      (node (ref "WEMOS1") (pin "D3") (pinfunction "D3/GP0_D3") (pintype "bidirectional"))
    )
    (net (code "84") (name "unconnected-(WEMOS1-D4{slash}LED-PadD4)") (class "Default")
      (node (ref "WEMOS1") (pin "D4") (pinfunction "D4/LED_D4") (pintype "bidirectional"))
    )
    (net (code "85") (name "unconnected-(WEMOS1-PadA0)") (class "Default")
      (node (ref "WEMOS1") (pin "A0") (pinfunction "A0_A0") (pintype "bidirectional"))
    )
    (net (code "86") (name "unconnected-(WEMOS1-PadRX)") (class "Default")
      (node (ref "WEMOS1") (pin "RX") (pinfunction "RX_RX") (pintype "bidirectional"))
    )
    (net (code "87") (name "unconnected-(WEMOS1-PadTX)") (class "Default")
      (node (ref "WEMOS1") (pin "TX") (pinfunction "TX_TX") (pintype "bidirectional"))
    )
  )
)
